# ADC088S022.net
KiCad netlist of a schematic drawn in Altium Designer
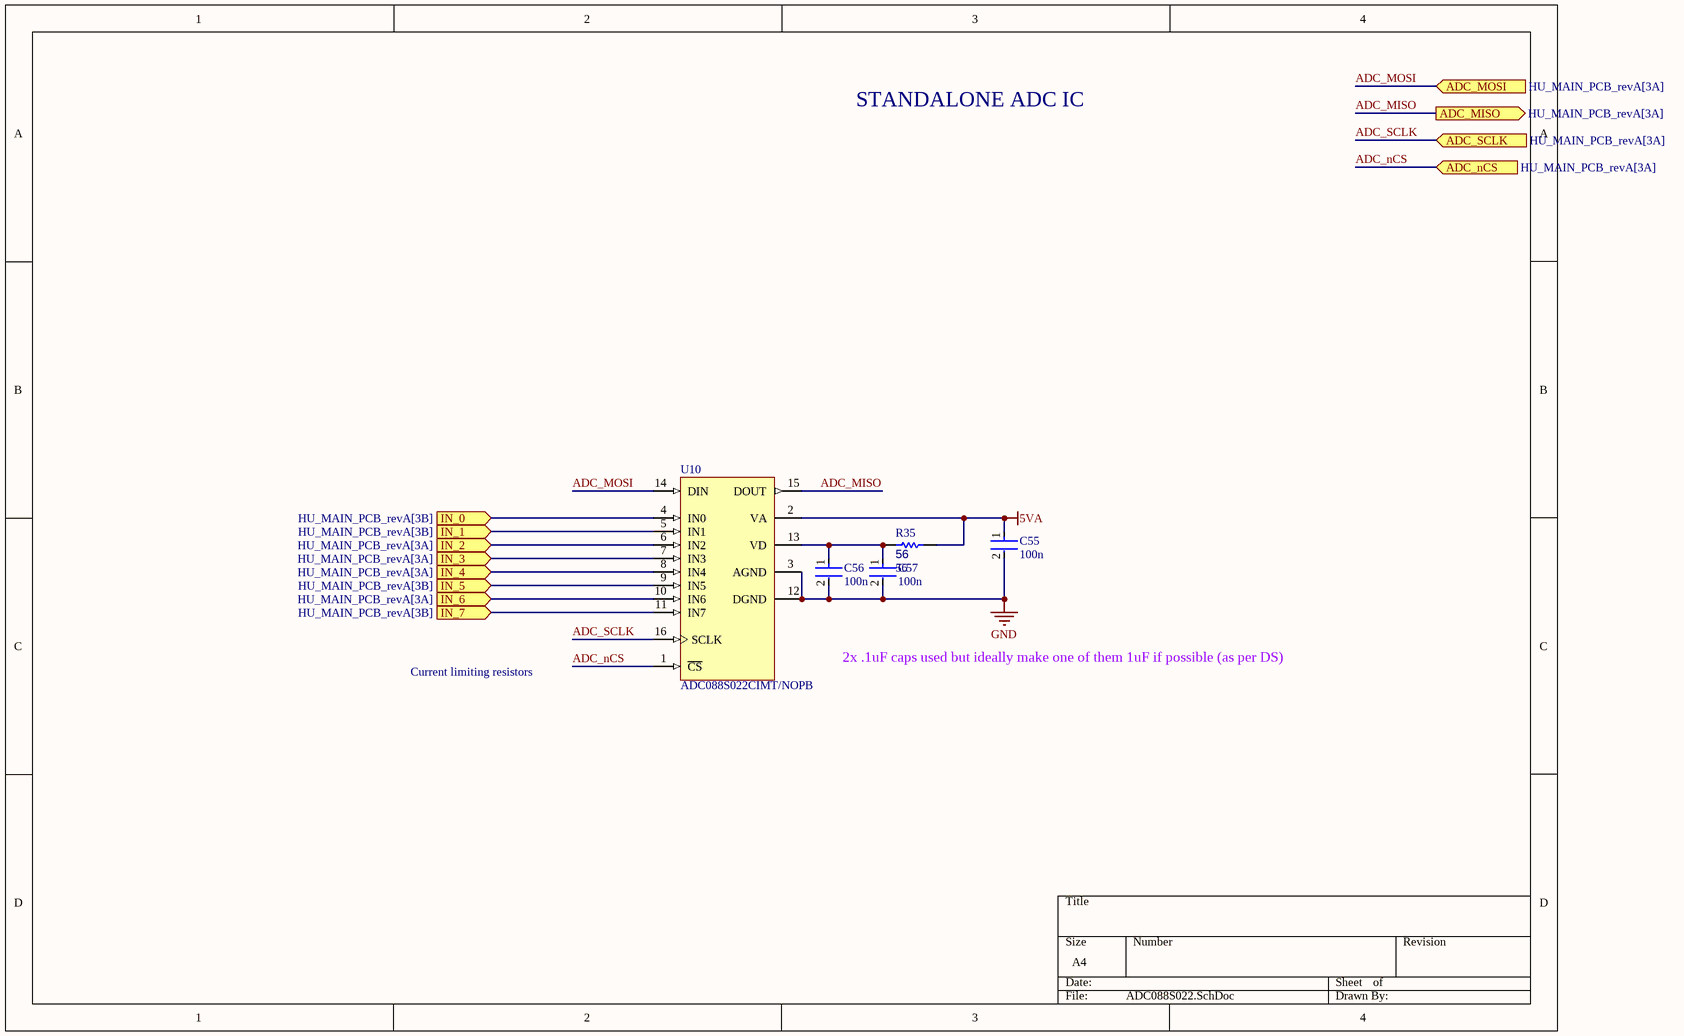
[diagram p0: ADC088S022.SchDoc]

(export (version "E")
  (design (tool "Eeschema 10.0.6"))
  (components
    (comp (ref "C55")
      (value "100n")
      (footprint "FP-0402-L_1_0_0_05-W_0_5-IPC_A")
      (description "LARGE PADS, 0402 CAP, CHANGE COMMENT TO MATCH REAL P/N")
      (libsource (lib "Space Concordia") (part "b4654b650e69147ec39a6b967a45e02"))
    )
    (comp (ref "C56")
      (value "100n")
      (footprint "FP-0402-L_1_0_0_05-W_0_5-IPC_A")
      (description "LARGE PADS, 0402 CAP, CHANGE COMMENT TO MATCH REAL P/N")
      (libsource (lib "Space Concordia") (part "b4654b650e69147ec39a6b967a45e02"))
    )
    (comp (ref "C57")
      (value "100n")
      (footprint "FP-0402-L_1_0_0_05-W_0_5-IPC_A")
      (description "LARGE PADS, 0402 CAP, CHANGE COMMENT TO MATCH REAL P/N")
      (libsource (lib "Space Concordia") (part "b4654b650e69147ec39a6b967a45e02"))
    )
    (comp (ref "R35")
      (value "56")
      (footprint "R0603B")
      (description "Resistor")
      (fields (field (name "ALTIUM_VALUE") "56"))
      (libsource (lib "Space Concordia") (part "Resistor"))
    )
    (comp (ref "U10")
      (value "ADC088S022CIMT/NOPB")
      (footprint "MTC16_L")
      (description "8-Channel, 50 kSPS to 200 kSPS, 8-Bit A/D Converter, 16-pin TSSOP, Pb-Free")
      (fields (field (name "MANUFACTURER") "National Semiconductor"))
      (libsource (lib "Altium Content Vault") (part "CON-ADC-ADC108S052CIMT"))
    )
  )
  (nets
    (net (code "1") (name "/ADC_MISO") (class "Default")
      (node (ref "U10") (pin "15") (pinfunction "DOUT_15") (pintype "output"))
    )
    (net (code "2") (name "/ADC_MOSI") (class "Default")
      (node (ref "U10") (pin "14") (pinfunction "DIN_14") (pintype "input"))
    )
    (net (code "3") (name "/ADC_SCLK") (class "Default")
      (node (ref "U10") (pin "16") (pinfunction "SCLK_16") (pintype "input"))
    )
    (net (code "4") (name "/ADC_nCS") (class "Default")
      (node (ref "U10") (pin "1") (pinfunction "~{CS}_1") (pintype "input"))
    )
    (net (code "5") (name "/IN_0") (class "Default")
      (node (ref "U10") (pin "4") (pinfunction "IN0_4") (pintype "input"))
    )
    (net (code "6") (name "/IN_1") (class "Default")
      (node (ref "U10") (pin "5") (pinfunction "IN1_5") (pintype "input"))
    )
    (net (code "7") (name "/IN_2") (class "Default")
      (node (ref "U10") (pin "6") (pinfunction "IN2_6") (pintype "input"))
    )
    (net (code "8") (name "/IN_3") (class "Default")
      (node (ref "U10") (pin "7") (pinfunction "IN3_7") (pintype "input"))
    )
    (net (code "9") (name "/IN_4") (class "Default")
      (node (ref "U10") (pin "8") (pinfunction "IN4_8") (pintype "input"))
    )
    (net (code "10") (name "/IN_5") (class "Default")
      (node (ref "U10") (pin "9") (pinfunction "IN5_9") (pintype "input"))
    )
    (net (code "11") (name "/IN_6") (class "Default")
      (node (ref "U10") (pin "10") (pinfunction "IN6_10") (pintype "input"))
    )
    (net (code "12") (name "/IN_7") (class "Default")
      (node (ref "U10") (pin "11") (pinfunction "IN7_11") (pintype "input"))
    )
    (net (code "13") (name "5VA") (class "Default")
      (node (ref "C55") (pin "1") (pinfunction "1_1") (pintype "passive"))
      (node (ref "R35") (pin "1") (pinfunction "1_1") (pintype "passive"))
      (node (ref "U10") (pin "2") (pinfunction "VA_2") (pintype "power_in"))
    )
    (net (code "14") (name "GND") (class "Default")
      (node (ref "C55") (pin "2") (pinfunction "2_2") (pintype "passive"))
      (node (ref "C56") (pin "2") (pinfunction "2_2") (pintype "passive"))
      (node (ref "C57") (pin "2") (pinfunction "2_2") (pintype "passive"))
      (node (ref "U10") (pin "12") (pinfunction "DGND_12") (pintype "power_in"))
      (node (ref "U10") (pin "3") (pinfunction "AGND_3") (pintype "power_in"))
    )
    (net (code "15") (name "Net-(U10-VD)") (class "Default")
      (node (ref "C56") (pin "1") (pinfunction "1_1") (pintype "passive"))
      (node (ref "C57") (pin "1") (pinfunction "1_1") (pintype "passive"))
      (node (ref "R35") (pin "2") (pinfunction "2_2") (pintype "passive"))
      (node (ref "U10") (pin "13") (pinfunction "VD_13") (pintype "power_in"))
    )
  )
)
